# Sheet1.net
KiCad netlist of a schematic drawn in Altium Designer
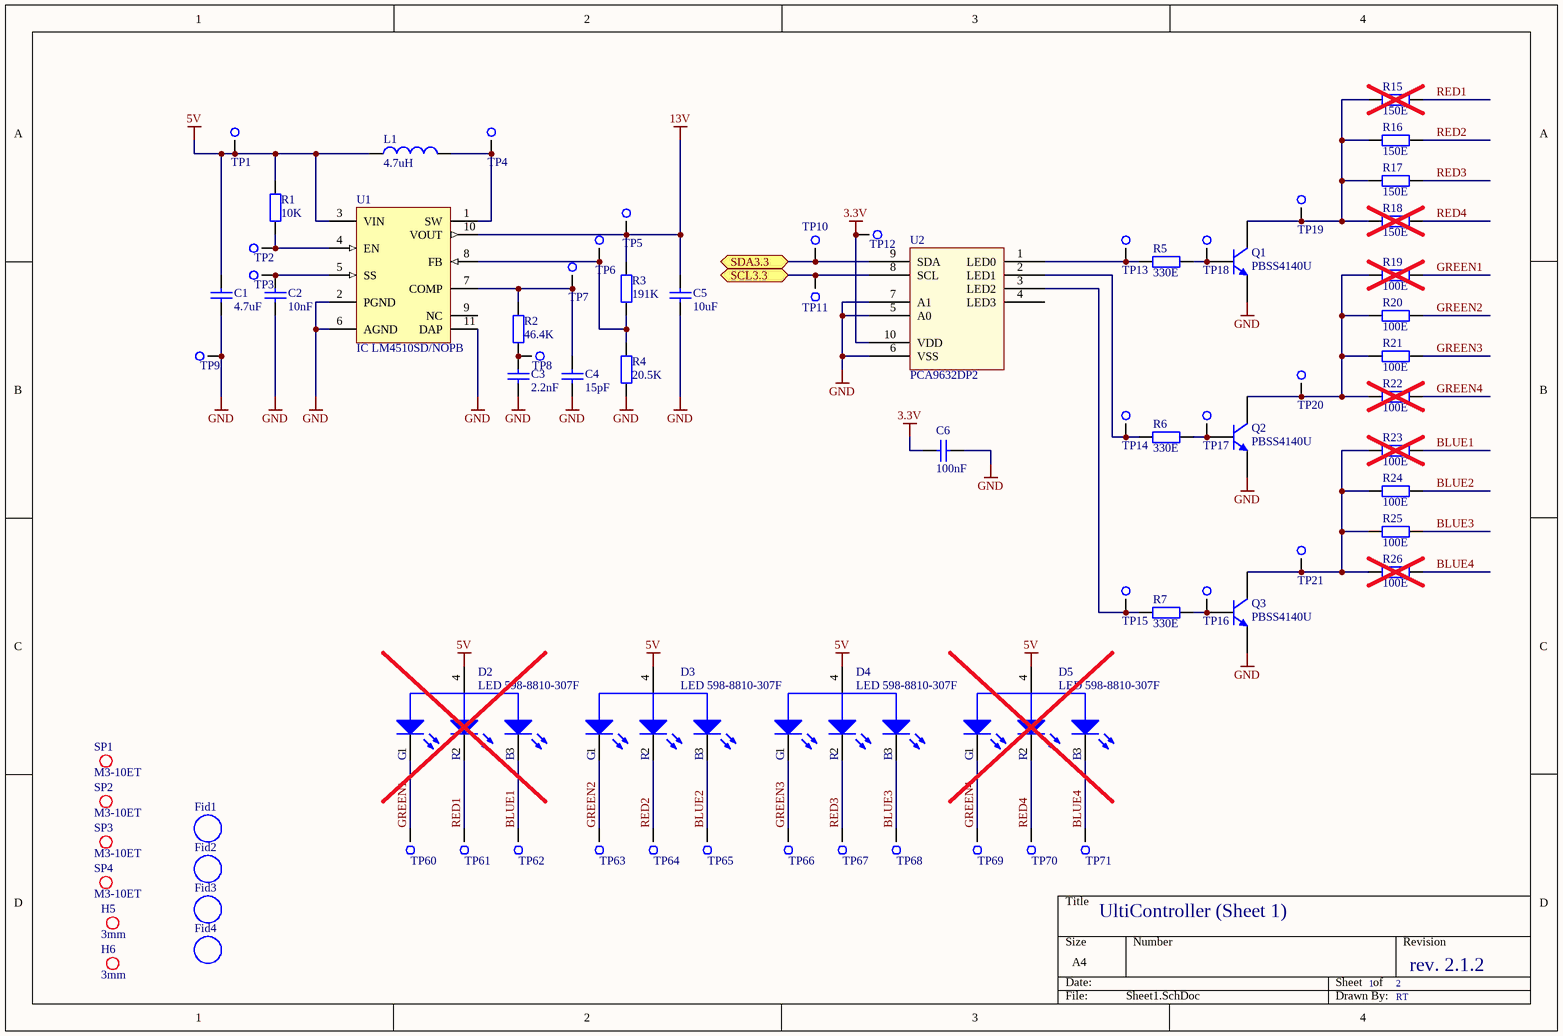
[diagram p0: Sheet1.SchDoc]

(export (version "E")
  (design (tool "Eeschema 10.0.6"))
  (components
    (comp (ref "C1")
      (value "4.7uF")
      (footprint "C1206 (3216)")
      (description "Cap 4.7uF 1206 X7R 10% 25V")
      (fields (field (name "MFG") "TDK"))
      (libsource (lib "Faber_SCH_lib") (part "Cap 4.7uF X7R 1206"))
    )
    (comp (ref "C2")
      (value "10nF")
      (footprint "C0805 (2012)")
      (description "Cap 10nF X7R 0805 10% 100V")
      (fields (field (name "MFG") "AVX"))
      (libsource (lib "Faber_SCH_lib") (part "Cap 10nF X7R 0805"))
    )
    (comp (ref "C3")
      (value "2.2nF")
      (footprint "C0805 (2012)")
      (description "Cap 2.2nF X7R 0805 10% 100V")
      (fields (field (name "MFG") "KEMET"))
      (libsource (lib "Faber_SCH_lib") (part "Cap 2.2nF X7R 0805"))
    )
    (comp (ref "C4")
      (value "15pF")
      (footprint "C0805 (2012)")
      (description "Cap 15pF NPO 0805 5% 100V")
      (fields (field (name "MFG") "AVX"))
      (libsource (lib "Faber_SCH_lib") (part "Cap 15pF NPO 0805"))
    )
    (comp (ref "C5")
      (value "10uF")
      (footprint "C1206 (3216)")
      (description "Cap 10uF 1206 X7R 10% 25V")
      (fields (field (name "MFG") "KEMET"))
      (libsource (lib "Faber_SCH_lib") (part "Cap 10uF X7R 1206"))
    )
    (comp (ref "C6")
      (value "100nF")
      (footprint "C0805 (2012)")
      (description "Cap 100nF X7R 0805 10% 100V")
      (fields (field (name "MFG") "AVX"))
      (libsource (lib "Faber_SCH_lib") (part "Cap 100nF X7R 0805"))
    )
    (comp (ref "D2")
      (value "LED 598-8810-307F")
      (footprint "LED SMD  598-8810-307F")
      (description "LED MULTICOLOR RED/GRN/BLUE 1208")
      (fields (field (name "MFG") "DIALIGHT"))
      (libsource (lib "Faber_SCH_lib") (part "LED 598-8810-307F"))
    )
    (comp (ref "D3")
      (value "LED 598-8810-307F")
      (footprint "LED SMD  598-8810-307F")
      (description "LED MULTICOLOR RED/GRN/BLUE 1208")
      (fields (field (name "MFG") "DIALIGHT"))
      (libsource (lib "Faber_SCH_lib") (part "LED 598-8810-307F"))
    )
    (comp (ref "D4")
      (value "LED 598-8810-307F")
      (footprint "LED SMD  598-8810-307F")
      (description "LED MULTICOLOR RED/GRN/BLUE 1208")
      (fields (field (name "MFG") "DIALIGHT"))
      (libsource (lib "Faber_SCH_lib") (part "LED 598-8810-307F"))
    )
    (comp (ref "D5")
      (value "LED 598-8810-307F")
      (footprint "LED SMD  598-8810-307F")
      (description "LED MULTICOLOR RED/GRN/BLUE 1208")
      (fields (field (name "MFG") "DIALIGHT"))
      (libsource (lib "Faber_SCH_lib") (part "LED 598-8810-307F"))
    )
    (comp (ref "Fid1")
      (value "Fiducial")
      (footprint "Fiducial 1,5mm")
      (libsource (lib "Faber_SCH_lib") (part "Fiducial"))
    )
    (comp (ref "Fid2")
      (value "Fiducial")
      (footprint "Fiducial 1,5mm")
      (libsource (lib "Faber_SCH_lib") (part "Fiducial"))
    )
    (comp (ref "Fid3")
      (value "Fiducial")
      (footprint "Fiducial 1,5mm")
      (libsource (lib "Faber_SCH_lib") (part "Fiducial"))
    )
    (comp (ref "Fid4")
      (value "Fiducial")
      (footprint "Fiducial 1,5mm")
      (libsource (lib "Faber_SCH_lib") (part "Fiducial"))
    )
    (comp (ref "H5")
      (value "3mm")
      (footprint "Mounting Hole 3mm PTH")
      (description "Mounting Hole 3mm PTH")
      (libsource (lib "Faber_SCH_lib") (part "Mounting Hole 3mm PTH"))
    )
    (comp (ref "H6")
      (value "3mm")
      (footprint "Mounting Hole 3mm PTH")
      (description "Mounting Hole 3mm PTH")
      (libsource (lib "Faber_SCH_lib") (part "Mounting Hole 3mm PTH"))
    )
    (comp (ref "L1")
      (value "4.7uH")
      (footprint "Inductor MCSDC0604")
      (description "Inductor 4.7uH SMD")
      (fields (field (name "MFG") "MULTICOMP"))
      (libsource (lib "Faber_SCH_lib") (part "Inductor 4.7uH SMD"))
    )
    (comp (ref "Q1")
      (value "PBSS4140U")
      (footprint "IC SOT323")
      (description "NPN PBSS4140U SOT-323 1A")
      (fields (field (name "MFG") "NXP"))
      (libsource (lib "Faber_SCH_lib") (part "NPN PBSS4140U"))
    )
    (comp (ref "Q2")
      (value "PBSS4140U")
      (footprint "IC SOT323")
      (description "NPN PBSS4140U SOT-323 1A")
      (fields (field (name "MFG") "NXP"))
      (libsource (lib "Faber_SCH_lib") (part "NPN PBSS4140U"))
    )
    (comp (ref "Q3")
      (value "PBSS4140U")
      (footprint "IC SOT323")
      (description "NPN PBSS4140U SOT-323 1A")
      (fields (field (name "MFG") "NXP"))
      (libsource (lib "Faber_SCH_lib") (part "NPN PBSS4140U"))
    )
    (comp (ref "R1")
      (value "10K")
      (footprint "R0805 (2012)")
      (description "Res 10K 0805 1% 100mW")
      (fields (field (name "MFG") "MULTICOMP"))
      (libsource (lib "Faber_SCH_lib") (part "Res 10K 0805"))
    )
    (comp (ref "R2")
      (value "46.4K")
      (footprint "R0805 (2012)")
      (description "Res 46.4K 0805 1% 100mW")
      (fields (field (name "MFG") "MULTICOMP"))
      (libsource (lib "Faber_SCH_lib") (part "Res 46.4K 0805"))
    )
    (comp (ref "R3")
      (value "191K")
      (footprint "R0805 (2012)")
      (description "Res 191K 0805 1% 125mW")
      (fields (field (name "MFG") "VISHAY DRALORIC"))
      (libsource (lib "Faber_SCH_lib") (part "Res 191K 0805"))
    )
    (comp (ref "R4")
      (value "20.5K")
      (footprint "R0805 (2012)")
      (description "Res 20.5K 0805 1% 100mW")
      (fields (field (name "MFG") "MULTICOMP"))
      (libsource (lib "Faber_SCH_lib") (part "Res 20.5K 0805"))
    )
    (comp (ref "R5")
      (value "330E")
      (footprint "R0805 (2012)")
      (description "Res 330E 0805 1% 100mW")
      (fields (field (name "MFG") "MULTICOMP"))
      (libsource (lib "Faber_SCH_lib") (part "Res 330E 0805"))
    )
    (comp (ref "R6")
      (value "330E")
      (footprint "R0805 (2012)")
      (description "Res 330E 0805 1% 100mW")
      (fields (field (name "MFG") "MULTICOMP"))
      (libsource (lib "Faber_SCH_lib") (part "Res 330E 0805"))
    )
    (comp (ref "R7")
      (value "330E")
      (footprint "R0805 (2012)")
      (description "Res 330E 0805 1% 100mW")
      (fields (field (name "MFG") "MULTICOMP"))
      (libsource (lib "Faber_SCH_lib") (part "Res 330E 0805"))
    )
    (comp (ref "R15")
      (value "150E")
      (footprint "R0805 (2012)")
      (description "Res 150E 0805 1% 125mW")
      (fields (field (name "MFG") "YAGEO"))
      (libsource (lib "Faber_SCH_lib") (part "Res 150E 0805"))
    )
    (comp (ref "R16")
      (value "150E")
      (footprint "R0805 (2012)")
      (description "Res 150E 0805 1% 125mW")
      (fields (field (name "MFG") "YAGEO"))
      (libsource (lib "Faber_SCH_lib") (part "Res 150E 0805"))
    )
    (comp (ref "R17")
      (value "150E")
      (footprint "R0805 (2012)")
      (description "Res 150E 0805 1% 125mW")
      (fields (field (name "MFG") "YAGEO"))
      (libsource (lib "Faber_SCH_lib") (part "Res 150E 0805"))
    )
    (comp (ref "R18")
      (value "150E")
      (footprint "R0805 (2012)")
      (description "Res 150E 0805 1% 125mW")
      (fields (field (name "MFG") "YAGEO"))
      (libsource (lib "Faber_SCH_lib") (part "Res 150E 0805"))
    )
    (comp (ref "R19")
      (value "100E")
      (footprint "R0805 (2012)")
      (description "Res 100E 0805 1% 125mW")
      (fields (field (name "MFG") "YAGEO"))
      (libsource (lib "Faber_SCH_lib") (part "Res 100E 0805"))
    )
    (comp (ref "R20")
      (value "100E")
      (footprint "R0805 (2012)")
      (description "Res 100E 0805 1% 125mW")
      (fields (field (name "MFG") "YAGEO"))
      (libsource (lib "Faber_SCH_lib") (part "Res 100E 0805"))
    )
    (comp (ref "R21")
      (value "100E")
      (footprint "R0805 (2012)")
      (description "Res 100E 0805 1% 125mW")
      (fields (field (name "MFG") "YAGEO"))
      (libsource (lib "Faber_SCH_lib") (part "Res 100E 0805"))
    )
    (comp (ref "R22")
      (value "100E")
      (footprint "R0805 (2012)")
      (description "Res 100E 0805 1% 125mW")
      (fields (field (name "MFG") "YAGEO"))
      (libsource (lib "Faber_SCH_lib") (part "Res 100E 0805"))
    )
    (comp (ref "R23")
      (value "100E")
      (footprint "R0805 (2012)")
      (description "Res 100E 0805 1% 125mW")
      (fields (field (name "MFG") "YAGEO"))
      (libsource (lib "Faber_SCH_lib") (part "Res 100E 0805"))
    )
    (comp (ref "R24")
      (value "100E")
      (footprint "R0805 (2012)")
      (description "Res 100E 0805 1% 125mW")
      (fields (field (name "MFG") "YAGEO"))
      (libsource (lib "Faber_SCH_lib") (part "Res 100E 0805"))
    )
    (comp (ref "R25")
      (value "100E")
      (footprint "R0805 (2012)")
      (description "Res 100E 0805 1% 125mW")
      (fields (field (name "MFG") "YAGEO"))
      (libsource (lib "Faber_SCH_lib") (part "Res 100E 0805"))
    )
    (comp (ref "R26")
      (value "100E")
      (footprint "R0805 (2012)")
      (description "Res 100E 0805 1% 125mW")
      (fields (field (name "MFG") "YAGEO"))
      (libsource (lib "Faber_SCH_lib") (part "Res 100E 0805"))
    )
    (comp (ref "SP1")
      (value "M3-10ET")
      (footprint "Spacer M3-10ET")
      (description "Spacer SMTSO-M3-10ET")
      (fields (field (name "MFG") "PEM"))
      (libsource (lib "Faber_SCH_lib") (part "Spacer M3-10ET"))
    )
    (comp (ref "SP2")
      (value "M3-10ET")
      (footprint "Spacer M3-10ET")
      (description "Spacer SMTSO-M3-10ET")
      (fields (field (name "MFG") "PEM"))
      (libsource (lib "Faber_SCH_lib") (part "Spacer M3-10ET"))
    )
    (comp (ref "SP3")
      (value "M3-10ET")
      (footprint "Spacer M3-10ET")
      (description "Spacer SMTSO-M3-10ET")
      (fields (field (name "MFG") "PEM"))
      (libsource (lib "Faber_SCH_lib") (part "Spacer M3-10ET"))
    )
    (comp (ref "SP4")
      (value "M3-10ET")
      (footprint "Spacer M3-10ET")
      (description "Spacer SMTSO-M3-10ET")
      (fields (field (name "MFG") "PEM"))
      (libsource (lib "Faber_SCH_lib") (part "Spacer M3-10ET"))
    )
    (comp (ref "TP1")
      (value "2mm")
      (footprint "TESTPOINT 2mm")
      (description "Testpoint, 2mm, round")
      (libsource (lib "Faber_SCH_lib") (part "Testpoint, 2mm, round"))
    )
    (comp (ref "TP2")
      (value "2mm")
      (footprint "TESTPOINT 2mm")
      (description "Testpoint, 2mm, round")
      (libsource (lib "Faber_SCH_lib") (part "Testpoint, 2mm, round"))
    )
    (comp (ref "TP3")
      (value "2mm")
      (footprint "TESTPOINT 2mm")
      (description "Testpoint, 2mm, round")
      (libsource (lib "Faber_SCH_lib") (part "Testpoint, 2mm, round"))
    )
    (comp (ref "TP4")
      (value "2mm")
      (footprint "TESTPOINT 2mm")
      (description "Testpoint, 2mm, round")
      (libsource (lib "Faber_SCH_lib") (part "Testpoint, 2mm, round"))
    )
    (comp (ref "TP5")
      (value "2mm")
      (footprint "TESTPOINT 2mm")
      (description "Testpoint, 2mm, round")
      (libsource (lib "Faber_SCH_lib") (part "Testpoint, 2mm, round"))
    )
    (comp (ref "TP6")
      (value "2mm")
      (footprint "TESTPOINT 2mm")
      (description "Testpoint, 2mm, round")
      (libsource (lib "Faber_SCH_lib") (part "Testpoint, 2mm, round"))
    )
    (comp (ref "TP7")
      (value "2mm")
      (footprint "TESTPOINT 2mm")
      (description "Testpoint, 2mm, round")
      (libsource (lib "Faber_SCH_lib") (part "Testpoint, 2mm, round"))
    )
    (comp (ref "TP8")
      (value "2mm")
      (footprint "TESTPOINT 2mm")
      (description "Testpoint, 2mm, round")
      (libsource (lib "Faber_SCH_lib") (part "Testpoint, 2mm, round"))
    )
    (comp (ref "TP9")
      (value "2mm")
      (footprint "TESTPOINT 2mm")
      (description "Testpoint, 2mm, round")
      (libsource (lib "Faber_SCH_lib") (part "Testpoint, 2mm, round"))
    )
    (comp (ref "TP10")
      (value "2mm")
      (footprint "TESTPOINT 2mm")
      (description "Testpoint, 2mm, round")
      (libsource (lib "Faber_SCH_lib") (part "Testpoint, 2mm, round"))
    )
    (comp (ref "TP11")
      (value "2mm")
      (footprint "TESTPOINT 2mm")
      (description "Testpoint, 2mm, round")
      (libsource (lib "Faber_SCH_lib") (part "Testpoint, 2mm, round"))
    )
    (comp (ref "TP12")
      (value "2mm")
      (footprint "TESTPOINT 2mm")
      (description "Testpoint, 2mm, round")
      (libsource (lib "Faber_SCH_lib") (part "Testpoint, 2mm, round"))
    )
    (comp (ref "TP13")
      (value "2mm")
      (footprint "TESTPOINT 2mm")
      (description "Testpoint, 2mm, round")
      (libsource (lib "Faber_SCH_lib") (part "Testpoint, 2mm, round"))
    )
    (comp (ref "TP14")
      (value "2mm")
      (footprint "TESTPOINT 2mm")
      (description "Testpoint, 2mm, round")
      (libsource (lib "Faber_SCH_lib") (part "Testpoint, 2mm, round"))
    )
    (comp (ref "TP15")
      (value "2mm")
      (footprint "TESTPOINT 2mm")
      (description "Testpoint, 2mm, round")
      (libsource (lib "Faber_SCH_lib") (part "Testpoint, 2mm, round"))
    )
    (comp (ref "TP16")
      (value "2mm")
      (footprint "TESTPOINT 2mm")
      (description "Testpoint, 2mm, round")
      (libsource (lib "Faber_SCH_lib") (part "Testpoint, 2mm, round"))
    )
    (comp (ref "TP17")
      (value "2mm")
      (footprint "TESTPOINT 2mm")
      (description "Testpoint, 2mm, round")
      (libsource (lib "Faber_SCH_lib") (part "Testpoint, 2mm, round"))
    )
    (comp (ref "TP18")
      (value "2mm")
      (footprint "TESTPOINT 2mm")
      (description "Testpoint, 2mm, round")
      (libsource (lib "Faber_SCH_lib") (part "Testpoint, 2mm, round"))
    )
    (comp (ref "TP19")
      (value "2mm")
      (footprint "TESTPOINT 2mm")
      (description "Testpoint, 2mm, round")
      (libsource (lib "Faber_SCH_lib") (part "Testpoint, 2mm, round"))
    )
    (comp (ref "TP20")
      (value "2mm")
      (footprint "TESTPOINT 2mm")
      (description "Testpoint, 2mm, round")
      (libsource (lib "Faber_SCH_lib") (part "Testpoint, 2mm, round"))
    )
    (comp (ref "TP21")
      (value "2mm")
      (footprint "TESTPOINT 2mm")
      (description "Testpoint, 2mm, round")
      (libsource (lib "Faber_SCH_lib") (part "Testpoint, 2mm, round"))
    )
    (comp (ref "TP60")
      (value "2mm")
      (footprint "TESTPOINT 2mm")
      (description "Testpoint, 2mm, round")
      (libsource (lib "Faber_SCH_lib") (part "Testpoint, 2mm, round"))
    )
    (comp (ref "TP61")
      (value "2mm")
      (footprint "TESTPOINT 2mm")
      (description "Testpoint, 2mm, round")
      (libsource (lib "Faber_SCH_lib") (part "Testpoint, 2mm, round"))
    )
    (comp (ref "TP62")
      (value "2mm")
      (footprint "TESTPOINT 2mm")
      (description "Testpoint, 2mm, round")
      (libsource (lib "Faber_SCH_lib") (part "Testpoint, 2mm, round"))
    )
    (comp (ref "TP63")
      (value "2mm")
      (footprint "TESTPOINT 2mm")
      (description "Testpoint, 2mm, round")
      (libsource (lib "Faber_SCH_lib") (part "Testpoint, 2mm, round"))
    )
    (comp (ref "TP64")
      (value "2mm")
      (footprint "TESTPOINT 2mm")
      (description "Testpoint, 2mm, round")
      (libsource (lib "Faber_SCH_lib") (part "Testpoint, 2mm, round"))
    )
    (comp (ref "TP65")
      (value "2mm")
      (footprint "TESTPOINT 2mm")
      (description "Testpoint, 2mm, round")
      (libsource (lib "Faber_SCH_lib") (part "Testpoint, 2mm, round"))
    )
    (comp (ref "TP66")
      (value "2mm")
      (footprint "TESTPOINT 2mm")
      (description "Testpoint, 2mm, round")
      (libsource (lib "Faber_SCH_lib") (part "Testpoint, 2mm, round"))
    )
    (comp (ref "TP67")
      (value "2mm")
      (footprint "TESTPOINT 2mm")
      (description "Testpoint, 2mm, round")
      (libsource (lib "Faber_SCH_lib") (part "Testpoint, 2mm, round"))
    )
    (comp (ref "TP68")
      (value "2mm")
      (footprint "TESTPOINT 2mm")
      (description "Testpoint, 2mm, round")
      (libsource (lib "Faber_SCH_lib") (part "Testpoint, 2mm, round"))
    )
    (comp (ref "TP69")
      (value "2mm")
      (footprint "TESTPOINT 2mm")
      (description "Testpoint, 2mm, round")
      (libsource (lib "Faber_SCH_lib") (part "Testpoint, 2mm, round"))
    )
    (comp (ref "TP70")
      (value "2mm")
      (footprint "TESTPOINT 2mm")
      (description "Testpoint, 2mm, round")
      (libsource (lib "Faber_SCH_lib") (part "Testpoint, 2mm, round"))
    )
    (comp (ref "TP71")
      (value "2mm")
      (footprint "TESTPOINT 2mm")
      (description "Testpoint, 2mm, round")
      (libsource (lib "Faber_SCH_lib") (part "Testpoint, 2mm, round"))
    )
    (comp (ref "U1")
      (value "IC LM4510SD/NOPB")
      (footprint "IC SDA10A")
      (description "IC Synchronous Step-Up DC/DC Converter with True Shutdown Isolation, 10-pin LLP, Pb-Free")
      (fields (field (name "MFG") "TEXAS INSTRUMENTS"))
      (libsource (lib "Faber_SCH_lib") (part "IC LM4510SD/NOPB"))
    )
    (comp (ref "U2")
      (value "PCA9632DP2")
      (footprint "IC TSSOP-10")
      (description "IC LED DRIVER RGBA")
      (fields (field (name "MFG") "NXP"))
      (libsource (lib "Faber_SCH_lib") (part "IC PCA9632"))
    )
  )
  (nets
    (net (code "1") (name "/BLUE1") (class "Default")
      (node (ref "D2") (pin "3") (pinfunction "3_3") (pintype "passive"))
      (node (ref "R23") (pin "2") (pinfunction "2_2") (pintype "passive"))
      (node (ref "TP62") (pin "1") (pinfunction "1_1") (pintype "passive"))
    )
    (net (code "2") (name "/BLUE2") (class "Default")
      (node (ref "D3") (pin "3") (pinfunction "3_3") (pintype "passive"))
      (node (ref "R24") (pin "2") (pinfunction "2_2") (pintype "passive"))
      (node (ref "TP65") (pin "1") (pinfunction "1_1") (pintype "passive"))
    )
    (net (code "3") (name "/BLUE3") (class "Default")
      (node (ref "D4") (pin "3") (pinfunction "3_3") (pintype "passive"))
      (node (ref "R25") (pin "2") (pinfunction "2_2") (pintype "passive"))
      (node (ref "TP68") (pin "1") (pinfunction "1_1") (pintype "passive"))
    )
    (net (code "4") (name "/BLUE4") (class "Default")
      (node (ref "D5") (pin "3") (pinfunction "3_3") (pintype "passive"))
      (node (ref "R26") (pin "2") (pinfunction "2_2") (pintype "passive"))
      (node (ref "TP71") (pin "1") (pinfunction "1_1") (pintype "passive"))
    )
    (net (code "5") (name "/GREEN1") (class "Default")
      (node (ref "D2") (pin "1") (pinfunction "1_1") (pintype "passive"))
      (node (ref "R19") (pin "2") (pinfunction "2_2") (pintype "passive"))
      (node (ref "TP60") (pin "1") (pinfunction "1_1") (pintype "passive"))
    )
    (net (code "6") (name "/GREEN2") (class "Default")
      (node (ref "D3") (pin "1") (pinfunction "1_1") (pintype "passive"))
      (node (ref "R20") (pin "2") (pinfunction "2_2") (pintype "passive"))
      (node (ref "TP63") (pin "1") (pinfunction "1_1") (pintype "passive"))
    )
    (net (code "7") (name "/GREEN3") (class "Default")
      (node (ref "D4") (pin "1") (pinfunction "1_1") (pintype "passive"))
      (node (ref "R21") (pin "2") (pinfunction "2_2") (pintype "passive"))
      (node (ref "TP66") (pin "1") (pinfunction "1_1") (pintype "passive"))
    )
    (net (code "8") (name "/GREEN4") (class "Default")
      (node (ref "D5") (pin "1") (pinfunction "1_1") (pintype "passive"))
      (node (ref "R22") (pin "2") (pinfunction "2_2") (pintype "passive"))
      (node (ref "TP69") (pin "1") (pinfunction "1_1") (pintype "passive"))
    )
    (net (code "9") (name "/RED1") (class "Default")
      (node (ref "D2") (pin "2") (pinfunction "2_2") (pintype "passive"))
      (node (ref "R15") (pin "2") (pinfunction "2_2") (pintype "passive"))
      (node (ref "TP61") (pin "1") (pinfunction "1_1") (pintype "passive"))
    )
    (net (code "10") (name "/RED2") (class "Default")
      (node (ref "D3") (pin "2") (pinfunction "2_2") (pintype "passive"))
      (node (ref "R16") (pin "2") (pinfunction "2_2") (pintype "passive"))
      (node (ref "TP64") (pin "1") (pinfunction "1_1") (pintype "passive"))
    )
    (net (code "11") (name "/RED3") (class "Default")
      (node (ref "D4") (pin "2") (pinfunction "2_2") (pintype "passive"))
      (node (ref "R17") (pin "2") (pinfunction "2_2") (pintype "passive"))
      (node (ref "TP67") (pin "1") (pinfunction "1_1") (pintype "passive"))
    )
    (net (code "12") (name "/RED4") (class "Default")
      (node (ref "D5") (pin "2") (pinfunction "2_2") (pintype "passive"))
      (node (ref "R18") (pin "2") (pinfunction "2_2") (pintype "passive"))
      (node (ref "TP70") (pin "1") (pinfunction "1_1") (pintype "passive"))
    )
    (net (code "13") (name "/SCL3.3") (class "Default")
      (node (ref "TP11") (pin "1") (pinfunction "1_1") (pintype "passive"))
      (node (ref "U2") (pin "8") (pinfunction "SCL_8") (pintype "passive"))
    )
    (net (code "14") (name "/SDA3.3") (class "Default")
      (node (ref "TP10") (pin "1") (pinfunction "1_1") (pintype "passive"))
      (node (ref "U2") (pin "9") (pinfunction "SDA_9") (pintype "passive"))
    )
    (net (code "15") (name "3.3V") (class "Default")
      (node (ref "C6") (pin "1") (pinfunction "1_1") (pintype "passive"))
      (node (ref "TP12") (pin "1") (pinfunction "1_1") (pintype "passive"))
      (node (ref "U2") (pin "10") (pinfunction "VDD_10") (pintype "passive"))
    )
    (net (code "16") (name "5V") (class "Default")
      (node (ref "C1") (pin "2") (pinfunction "2_2") (pintype "passive"))
      (node (ref "D2") (pin "4") (pinfunction "4_4") (pintype "passive"))
      (node (ref "D3") (pin "4") (pinfunction "4_4") (pintype "passive"))
      (node (ref "D4") (pin "4") (pinfunction "4_4") (pintype "passive"))
      (node (ref "D5") (pin "4") (pinfunction "4_4") (pintype "passive"))
      (node (ref "L1") (pin "1") (pinfunction "1_1") (pintype "passive"))
      (node (ref "R1") (pin "2") (pinfunction "2_2") (pintype "passive"))
      (node (ref "TP1") (pin "1") (pinfunction "1_1") (pintype "passive"))
      (node (ref "U1") (pin "3") (pinfunction "VIN_3") (pintype "power_in"))
    )
    (net (code "17") (name "13V") (class "Default")
      (node (ref "C5") (pin "2") (pinfunction "2_2") (pintype "passive"))
      (node (ref "R3") (pin "2") (pinfunction "2_2") (pintype "passive"))
      (node (ref "TP5") (pin "1") (pinfunction "1_1") (pintype "passive"))
      (node (ref "U1") (pin "10") (pinfunction "VOUT_10") (pintype "output"))
    )
    (net (code "18") (name "GND") (class "Default")
      (node (ref "C1") (pin "1") (pinfunction "1_1") (pintype "passive"))
      (node (ref "C2") (pin "1") (pinfunction "1_1") (pintype "passive"))
      (node (ref "C3") (pin "1") (pinfunction "1_1") (pintype "passive"))
      (node (ref "C4") (pin "1") (pinfunction "1_1") (pintype "passive"))
      (node (ref "C5") (pin "1") (pinfunction "1_1") (pintype "passive"))
      (node (ref "C6") (pin "2") (pinfunction "2_2") (pintype "passive"))
      (node (ref "Q1") (pin "2") (pinfunction "E_2") (pintype "passive"))
      (node (ref "Q2") (pin "2") (pinfunction "E_2") (pintype "passive"))
      (node (ref "Q3") (pin "2") (pinfunction "E_2") (pintype "passive"))
      (node (ref "R4") (pin "1") (pinfunction "1_1") (pintype "passive"))
      (node (ref "TP9") (pin "1") (pinfunction "1_1") (pintype "passive"))
      (node (ref "U1") (pin "11") (pinfunction "DAP_11") (pintype "power_in"))
      (node (ref "U1") (pin "2") (pinfunction "PGND_2") (pintype "power_in"))
      (node (ref "U1") (pin "6") (pinfunction "AGND_6") (pintype "power_in"))
      (node (ref "U2") (pin "5") (pinfunction "A0_5") (pintype "passive"))
      (node (ref "U2") (pin "6") (pinfunction "VSS_6") (pintype "passive"))
      (node (ref "U2") (pin "7") (pinfunction "A1_7") (pintype "passive"))
    )
    (net (code "19") (name "Net-(C3-Pad2)") (class "Default")
      (node (ref "C3") (pin "2") (pinfunction "2_2") (pintype "passive"))
      (node (ref "R2") (pin "1") (pinfunction "1_1") (pintype "passive"))
      (node (ref "TP8") (pin "1") (pinfunction "1_1") (pintype "passive"))
    )
    (net (code "20") (name "Net-(Q1-B)") (class "Default")
      (node (ref "Q1") (pin "1") (pinfunction "B_1") (pintype "passive"))
      (node (ref "R5") (pin "2") (pinfunction "2_2") (pintype "passive"))
      (node (ref "TP18") (pin "1") (pinfunction "1_1") (pintype "passive"))
    )
    (net (code "21") (name "Net-(Q1-C)") (class "Default")
      (node (ref "Q1") (pin "3") (pinfunction "C_3") (pintype "passive"))
      (node (ref "R15") (pin "1") (pinfunction "1_1") (pintype "passive"))
      (node (ref "R16") (pin "1") (pinfunction "1_1") (pintype "passive"))
      (node (ref "R17") (pin "1") (pinfunction "1_1") (pintype "passive"))
      (node (ref "R18") (pin "1") (pinfunction "1_1") (pintype "passive"))
      (node (ref "TP19") (pin "1") (pinfunction "1_1") (pintype "passive"))
    )
    (net (code "22") (name "Net-(Q2-B)") (class "Default")
      (node (ref "Q2") (pin "1") (pinfunction "B_1") (pintype "passive"))
      (node (ref "R6") (pin "2") (pinfunction "2_2") (pintype "passive"))
      (node (ref "TP17") (pin "1") (pinfunction "1_1") (pintype "passive"))
    )
    (net (code "23") (name "Net-(Q2-C)") (class "Default")
      (node (ref "Q2") (pin "3") (pinfunction "C_3") (pintype "passive"))
      (node (ref "R19") (pin "1") (pinfunction "1_1") (pintype "passive"))
      (node (ref "R20") (pin "1") (pinfunction "1_1") (pintype "passive"))
      (node (ref "R21") (pin "1") (pinfunction "1_1") (pintype "passive"))
      (node (ref "R22") (pin "1") (pinfunction "1_1") (pintype "passive"))
      (node (ref "TP20") (pin "1") (pinfunction "1_1") (pintype "passive"))
    )
    (net (code "24") (name "Net-(Q3-B)") (class "Default")
      (node (ref "Q3") (pin "1") (pinfunction "B_1") (pintype "passive"))
      (node (ref "R7") (pin "2") (pinfunction "2_2") (pintype "passive"))
      (node (ref "TP16") (pin "1") (pinfunction "1_1") (pintype "passive"))
    )
    (net (code "25") (name "Net-(Q3-C)") (class "Default")
      (node (ref "Q3") (pin "3") (pinfunction "C_3") (pintype "passive"))
      (node (ref "R23") (pin "1") (pinfunction "1_1") (pintype "passive"))
      (node (ref "R24") (pin "1") (pinfunction "1_1") (pintype "passive"))
      (node (ref "R25") (pin "1") (pinfunction "1_1") (pintype "passive"))
      (node (ref "R26") (pin "1") (pinfunction "1_1") (pintype "passive"))
      (node (ref "TP21") (pin "1") (pinfunction "1_1") (pintype "passive"))
    )
    (net (code "26") (name "Net-(U1-COMP)") (class "Default")
      (node (ref "C4") (pin "2") (pinfunction "2_2") (pintype "passive"))
      (node (ref "R2") (pin "2") (pinfunction "2_2") (pintype "passive"))
      (node (ref "TP7") (pin "1") (pinfunction "1_1") (pintype "passive"))
      (node (ref "U1") (pin "7") (pinfunction "COMP_7") (pintype "passive"))
    )
    (net (code "27") (name "Net-(U1-EN)") (class "Default")
      (node (ref "R1") (pin "1") (pinfunction "1_1") (pintype "passive"))
      (node (ref "TP2") (pin "1") (pinfunction "1_1") (pintype "passive"))
      (node (ref "U1") (pin "4") (pinfunction "EN_4") (pintype "input"))
    )
    (net (code "28") (name "Net-(U1-FB)") (class "Default")
      (node (ref "R3") (pin "1") (pinfunction "1_1") (pintype "passive"))
      (node (ref "R4") (pin "2") (pinfunction "2_2") (pintype "passive"))
      (node (ref "TP6") (pin "1") (pinfunction "1_1") (pintype "passive"))
      (node (ref "U1") (pin "8") (pinfunction "FB_8") (pintype "input"))
    )
    (net (code "29") (name "Net-(U1-SS)") (class "Default")
      (node (ref "C2") (pin "2") (pinfunction "2_2") (pintype "passive"))
      (node (ref "TP3") (pin "1") (pinfunction "1_1") (pintype "passive"))
      (node (ref "U1") (pin "5") (pinfunction "SS_5") (pintype "input"))
    )
    (net (code "30") (name "Net-(U1-SW)") (class "Default")
      (node (ref "L1") (pin "2") (pinfunction "2_2") (pintype "passive"))
      (node (ref "TP4") (pin "1") (pinfunction "1_1") (pintype "passive"))
      (node (ref "U1") (pin "1") (pinfunction "SW_1") (pintype "power_in"))
    )
    (net (code "31") (name "Net-(U2-LED0)") (class "Default")
      (node (ref "R5") (pin "1") (pinfunction "1_1") (pintype "passive"))
      (node (ref "TP13") (pin "1") (pinfunction "1_1") (pintype "passive"))
      (node (ref "U2") (pin "1") (pinfunction "LED0_1") (pintype "passive"))
    )
    (net (code "32") (name "Net-(U2-LED1)") (class "Default")
      (node (ref "R6") (pin "1") (pinfunction "1_1") (pintype "passive"))
      (node (ref "TP14") (pin "1") (pinfunction "1_1") (pintype "passive"))
      (node (ref "U2") (pin "2") (pinfunction "LED1_2") (pintype "passive"))
    )
    (net (code "33") (name "Net-(U2-LED2)") (class "Default")
      (node (ref "R7") (pin "1") (pinfunction "1_1") (pintype "passive"))
      (node (ref "TP15") (pin "1") (pinfunction "1_1") (pintype "passive"))
      (node (ref "U2") (pin "3") (pinfunction "LED2_3") (pintype "passive"))
    )
    (net (code "34") (name "unconnected-(U1-NC-Pad9)") (class "Default")
      (node (ref "U1") (pin "9") (pinfunction "NC_9") (pintype "passive"))
    )
    (net (code "35") (name "unconnected-(U2-LED3-Pad4)") (class "Default")
      (node (ref "U2") (pin "4") (pinfunction "LED3_4") (pintype "passive"))
    )
  )
)
